# sensor-multichannel.net
KiCad netlist of a schematic drawn in EAGLE
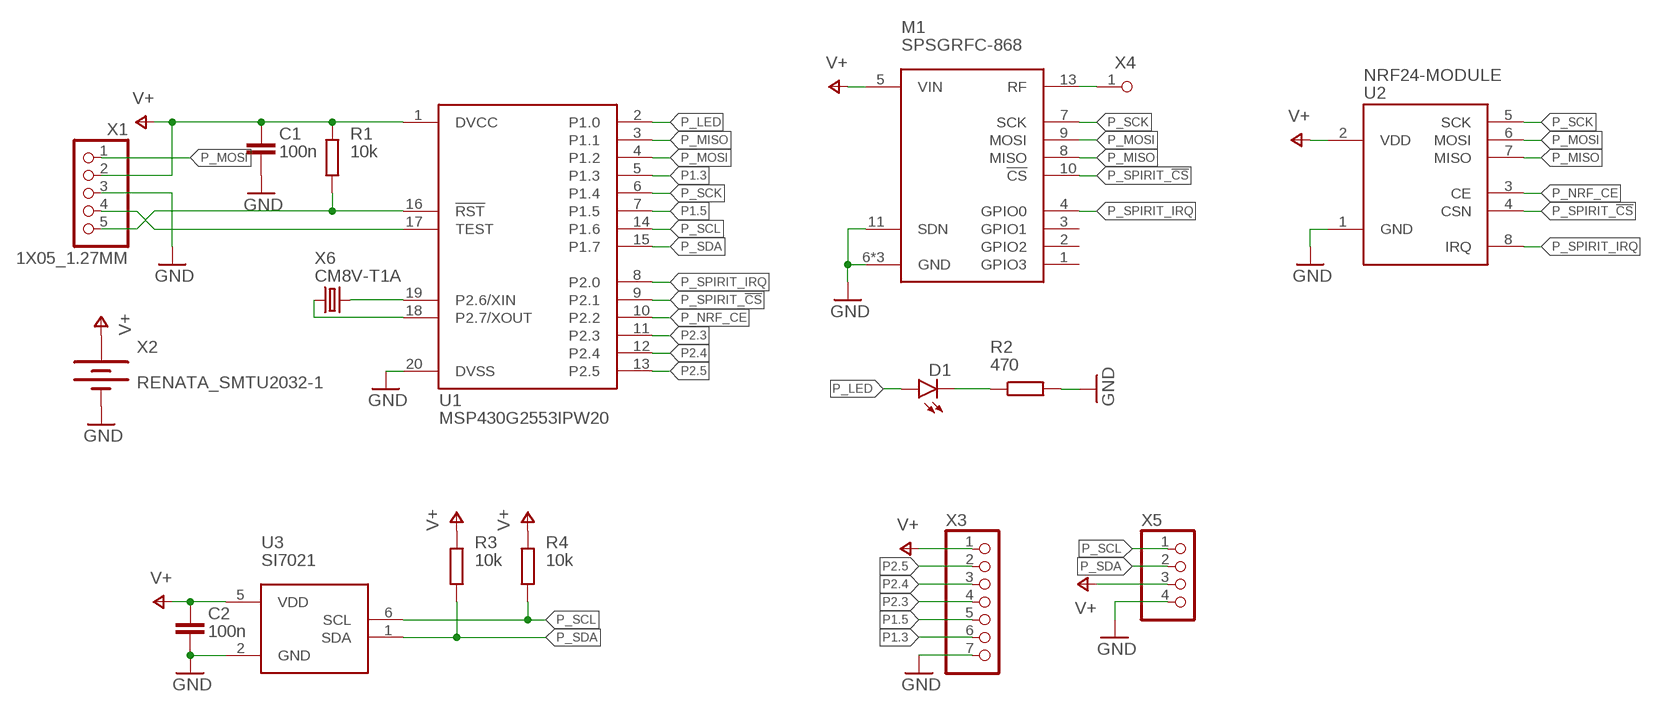
[diagram p0: schematic, sheet 1]

(export (version "E")
  (design (tool "Eeschema 10.0.6"))
  (components
    (comp (ref "C1")
      (value "100n")
      (footprint "eagle-import:C0603")
      (libsource (lib "eagle-import") (part "C0603"))
    )
    (comp (ref "C2")
      (value "100n")
      (footprint "eagle-import:C0603")
      (libsource (lib "eagle-import") (part "C0603"))
    )
    (comp (ref "D1")
      (value "LEDCHIPLED_0805")
      (footprint "eagle-import:CHIPLED_0805")
      (libsource (lib "eagle-import") (part "LEDCHIPLED_0805"))
    )
    (comp (ref "M1")
      (value "SPSGRFC-868")
      (footprint "eagle-import:SPSGRFC-868")
      (libsource (lib "eagle-import") (part "SPSGRFC-868"))
    )
    (comp (ref "R1")
      (value "10k")
      (footprint "eagle-import:R0603")
      (libsource (lib "eagle-import") (part "R0603"))
    )
    (comp (ref "R2")
      (value "470")
      (footprint "eagle-import:R0603")
      (libsource (lib "eagle-import") (part "R0603"))
    )
    (comp (ref "R3")
      (value "10k")
      (footprint "eagle-import:R0603")
      (libsource (lib "eagle-import") (part "R0603"))
    )
    (comp (ref "R4")
      (value "10k")
      (footprint "eagle-import:R0603")
      (libsource (lib "eagle-import") (part "R0603"))
    )
    (comp (ref "U1")
      (value "MSP430G2553IPW20")
      (footprint "eagle-import:PW20")
      (libsource (lib "eagle-import") (part "MSP430G2553IPW20"))
    )
    (comp (ref "U2")
      (value "NRF24-MODULE")
      (footprint "eagle-import:NRF24-MODULE")
      (libsource (lib "eagle-import") (part "NRF24-MODULE"))
    )
    (comp (ref "U3")
      (value "SI7021")
      (footprint "eagle-import:DFN6-3X3")
      (libsource (lib "eagle-import") (part "SI7021"))
    )
    (comp (ref "X1")
      (value "1X05_1.27MM")
      (footprint "eagle-import:1X05_1.27MM")
      (libsource (lib "eagle-import") (part "1X05_1.27MM"))
    )
    (comp (ref "X2")
      (value "RENATA_SMTU2032-1")
      (footprint "eagle-import:RENATA_SMTU2032-1")
      (libsource (lib "eagle-import") (part "RENATA_SMTU2032-1"))
    )
    (comp (ref "X3")
      (value "PINHD_7_RNDNS")
      (footprint "eagle-import:1X07_NOSILK")
      (libsource (lib "eagle-import") (part "PINHD_7_RNDNS"))
    )
    (comp (ref "X4")
      (value "PINHD_1_RND")
      (footprint "eagle-import:1X01_NOSILK")
      (libsource (lib "eagle-import") (part "PINHD_1_RND"))
    )
    (comp (ref "X5")
      (value "PINHD_4_RNDNS")
      (footprint "eagle-import:1X04_NOSILK")
      (libsource (lib "eagle-import") (part "PINHD_4_RNDNS"))
    )
    (comp (ref "X6")
      (value "CM8V-T1A")
      (footprint "eagle-import:CM8V-T1A")
      (libsource (lib "eagle-import") (part "CM8V-T1A"))
    )
  )
  (nets
    (net (code "1") (name "/P_SPIRIT_~{CS}") (class "Default")
      (node (ref "M1") (pin "10") (pinfunction "~{CS}_10") (pintype "input"))
      (node (ref "U1") (pin "9") (pinfunction "P2.1_9") (pintype "bidirectional"))
      (node (ref "U2") (pin "4") (pinfunction "CSN_4") (pintype "bidirectional"))
    )
    (net (code "2") (name "GND") (class "Default")
      (node (ref "C1") (pin "2") (pinfunction "2_2") (pintype "passive"))
      (node (ref "C2") (pin "2") (pinfunction "2_2") (pintype "passive"))
      (node (ref "M1") (pin "11") (pinfunction "SDN_11") (pintype "input"))
      (node (ref "M1") (pin "12") (pinfunction "GND_12") (pintype "power_in"))
      (node (ref "M1") (pin "14") (pinfunction "GND_14") (pintype "power_in"))
      (node (ref "M1") (pin "6") (pinfunction "GND_6") (pintype "power_in"))
      (node (ref "R2") (pin "2") (pinfunction "2_2") (pintype "passive"))
      (node (ref "U1") (pin "20") (pinfunction "DVSS_20") (pintype "bidirectional"))
      (node (ref "U2") (pin "1") (pinfunction "GND_1") (pintype "bidirectional"))
      (node (ref "U3") (pin "2") (pinfunction "GND_2") (pintype "power_in"))
      (node (ref "X1") (pin "3") (pinfunction "3_3") (pintype "passive"))
      (node (ref "X2") (pin "2") (pinfunction "-_2") (pintype "power_in"))
      (node (ref "X3") (pin "7") (pinfunction "7_7") (pintype "passive"))
      (node (ref "X5") (pin "4") (pinfunction "4_4") (pintype "passive"))
    )
    (net (code "3") (name "Net-(D1-PadC)") (class "Default")
      (node (ref "D1") (pin "C") (pinfunction "C_C") (pintype "passive"))
      (node (ref "R2") (pin "1") (pinfunction "1_1") (pintype "passive"))
    )
    (net (code "4") (name "Net-(M1-RF)") (class "Default")
      (node (ref "M1") (pin "13") (pinfunction "RF_13") (pintype "bidirectional"))
      (node (ref "X4") (pin "1") (pinfunction "1_1") (pintype "passive"))
    )
    (net (code "5") (name "Net-(U1-P2.6{slash}XIN)") (class "Default")
      (node (ref "U1") (pin "19") (pinfunction "P2.6/XIN_19") (pintype "bidirectional"))
      (node (ref "X6") (pin "P$2") (pinfunction "2_P$2") (pintype "passive"))
    )
    (net (code "6") (name "Net-(U1-P2.7{slash}XOUT)") (class "Default")
      (node (ref "U1") (pin "18") (pinfunction "P2.7/XOUT_18") (pintype "bidirectional"))
      (node (ref "X6") (pin "P$1") (pinfunction "1_P$1") (pintype "passive"))
    )
    (net (code "7") (name "Net-(U1-TEST)") (class "Default")
      (node (ref "U1") (pin "17") (pinfunction "TEST_17") (pintype "bidirectional"))
      (node (ref "X1") (pin "4") (pinfunction "4_4") (pintype "passive"))
    )
    (net (code "8") (name "Net-(U1-~{RST})") (class "Default")
      (node (ref "R1") (pin "1") (pinfunction "1_1") (pintype "passive"))
      (node (ref "U1") (pin "16") (pinfunction "~{RST}_16") (pintype "bidirectional"))
      (node (ref "X1") (pin "5") (pinfunction "5_5") (pintype "passive"))
    )
    (net (code "9") (name "P1.3") (class "Default")
      (node (ref "U1") (pin "5") (pinfunction "P1.3_5") (pintype "bidirectional"))
      (node (ref "X3") (pin "6") (pinfunction "6_6") (pintype "passive"))
    )
    (net (code "10") (name "P1.5") (class "Default")
      (node (ref "U1") (pin "7") (pinfunction "P1.5_7") (pintype "bidirectional"))
      (node (ref "X3") (pin "5") (pinfunction "5_5") (pintype "passive"))
    )
    (net (code "11") (name "P2.3") (class "Default")
      (node (ref "U1") (pin "11") (pinfunction "P2.3_11") (pintype "bidirectional"))
      (node (ref "X3") (pin "4") (pinfunction "4_4") (pintype "passive"))
    )
    (net (code "12") (name "P2.4") (class "Default")
      (node (ref "U1") (pin "12") (pinfunction "P2.4_12") (pintype "bidirectional"))
      (node (ref "X3") (pin "3") (pinfunction "3_3") (pintype "passive"))
    )
    (net (code "13") (name "P2.5") (class "Default")
      (node (ref "U1") (pin "13") (pinfunction "P2.5_13") (pintype "bidirectional"))
      (node (ref "X3") (pin "2") (pinfunction "2_2") (pintype "passive"))
    )
    (net (code "14") (name "P_LED") (class "Default")
      (node (ref "D1") (pin "A") (pinfunction "A_A") (pintype "passive"))
      (node (ref "U1") (pin "2") (pinfunction "P1.0_2") (pintype "bidirectional"))
    )
    (net (code "15") (name "P_MISO") (class "Default")
      (node (ref "M1") (pin "8") (pinfunction "MISO_8") (pintype "bidirectional"))
      (node (ref "U1") (pin "3") (pinfunction "P1.1_3") (pintype "bidirectional"))
      (node (ref "U2") (pin "7") (pinfunction "MISO_7") (pintype "bidirectional"))
    )
    (net (code "16") (name "P_MOSI") (class "Default")
      (node (ref "M1") (pin "9") (pinfunction "MOSI_9") (pintype "input"))
      (node (ref "U1") (pin "4") (pinfunction "P1.2_4") (pintype "bidirectional"))
      (node (ref "U2") (pin "6") (pinfunction "MOSI_6") (pintype "bidirectional"))
      (node (ref "X1") (pin "1") (pinfunction "1_1") (pintype "passive"))
    )
    (net (code "17") (name "P_NRF_CE") (class "Default")
      (node (ref "U1") (pin "10") (pinfunction "P2.2_10") (pintype "bidirectional"))
      (node (ref "U2") (pin "3") (pinfunction "CE_3") (pintype "bidirectional"))
    )
    (net (code "18") (name "P_SCK") (class "Default")
      (node (ref "M1") (pin "7") (pinfunction "SCK_7") (pintype "input"))
      (node (ref "U1") (pin "6") (pinfunction "P1.4_6") (pintype "bidirectional"))
      (node (ref "U2") (pin "5") (pinfunction "SCK_5") (pintype "bidirectional"))
    )
    (net (code "19") (name "P_SCL") (class "Default")
      (node (ref "R4") (pin "1") (pinfunction "1_1") (pintype "passive"))
      (node (ref "U1") (pin "14") (pinfunction "P1.6_14") (pintype "bidirectional"))
      (node (ref "U3") (pin "6") (pinfunction "SCL_6") (pintype "input"))
      (node (ref "X5") (pin "1") (pinfunction "1_1") (pintype "passive"))
    )
    (net (code "20") (name "P_SDA") (class "Default")
      (node (ref "R3") (pin "1") (pinfunction "1_1") (pintype "passive"))
      (node (ref "U1") (pin "15") (pinfunction "P1.7_15") (pintype "bidirectional"))
      (node (ref "U3") (pin "1") (pinfunction "SDA_1") (pintype "input"))
      (node (ref "X5") (pin "2") (pinfunction "2_2") (pintype "passive"))
    )
    (net (code "21") (name "P_SPIRIT_IRQ") (class "Default")
      (node (ref "M1") (pin "4") (pinfunction "GPIO0_4") (pintype "bidirectional"))
      (node (ref "U1") (pin "8") (pinfunction "P2.0_8") (pintype "bidirectional"))
      (node (ref "U2") (pin "8") (pinfunction "IRQ_8") (pintype "bidirectional"))
    )
    (net (code "22") (name "V+") (class "Default")
      (node (ref "C1") (pin "1") (pinfunction "1_1") (pintype "passive"))
      (node (ref "C2") (pin "1") (pinfunction "1_1") (pintype "passive"))
      (node (ref "M1") (pin "5") (pinfunction "VIN_5") (pintype "power_in"))
      (node (ref "R1") (pin "2") (pinfunction "2_2") (pintype "passive"))
      (node (ref "R3") (pin "2") (pinfunction "2_2") (pintype "passive"))
      (node (ref "R4") (pin "2") (pinfunction "2_2") (pintype "passive"))
      (node (ref "U1") (pin "1") (pinfunction "DVCC_1") (pintype "bidirectional"))
      (node (ref "U2") (pin "2") (pinfunction "VDD_2") (pintype "bidirectional"))
      (node (ref "U3") (pin "5") (pinfunction "VDD_5") (pintype "input"))
      (node (ref "X1") (pin "2") (pinfunction "2_2") (pintype "passive"))
      (node (ref "X2") (pin "1") (pinfunction "+_1") (pintype "power_in"))
      (node (ref "X3") (pin "1") (pinfunction "1_1") (pintype "passive"))
      (node (ref "X5") (pin "3") (pinfunction "3_3") (pintype "passive"))
    )
    (net (code "23") (name "unconnected-(M1-GPIO1-Pad3)") (class "Default")
      (node (ref "M1") (pin "3") (pinfunction "GPIO1_3") (pintype "bidirectional"))
    )
    (net (code "24") (name "unconnected-(M1-GPIO2-Pad2)") (class "Default")
      (node (ref "M1") (pin "2") (pinfunction "GPIO2_2") (pintype "bidirectional"))
    )
    (net (code "25") (name "unconnected-(M1-GPIO3-Pad1)") (class "Default")
      (node (ref "M1") (pin "1") (pinfunction "GPIO3_1") (pintype "bidirectional"))
    )
  )
)
